# qtwo_schem.net
KiCad netlist of a schematic drawn in EAGLE
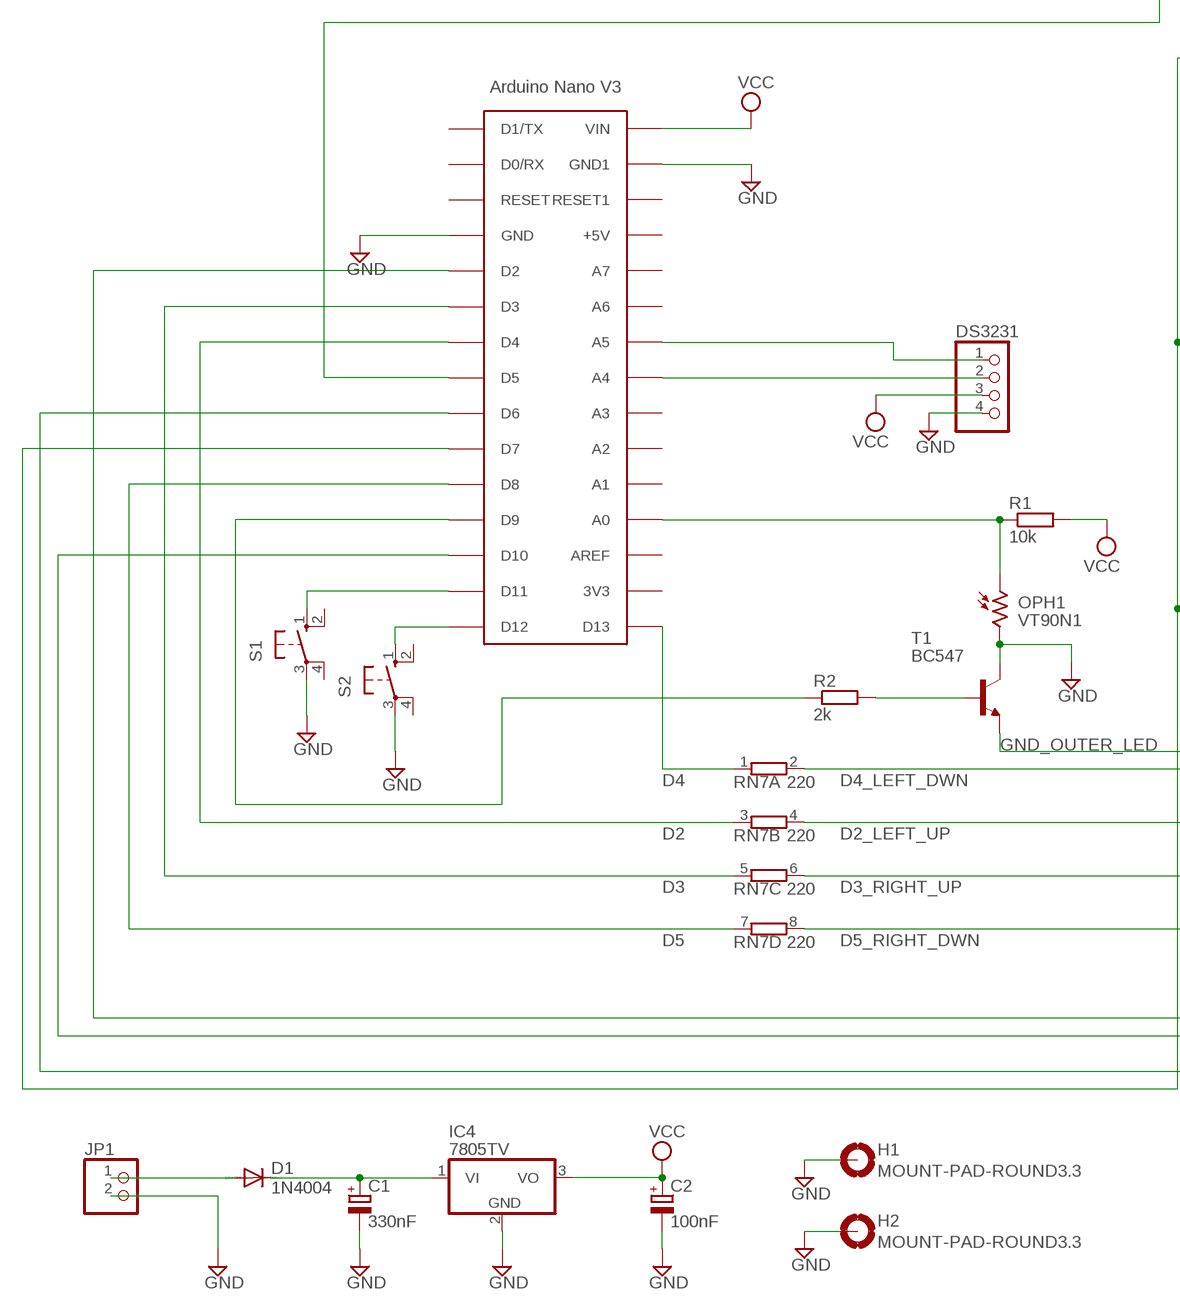
[diagram p0: schematic, sheet 1, part 1 of 2]
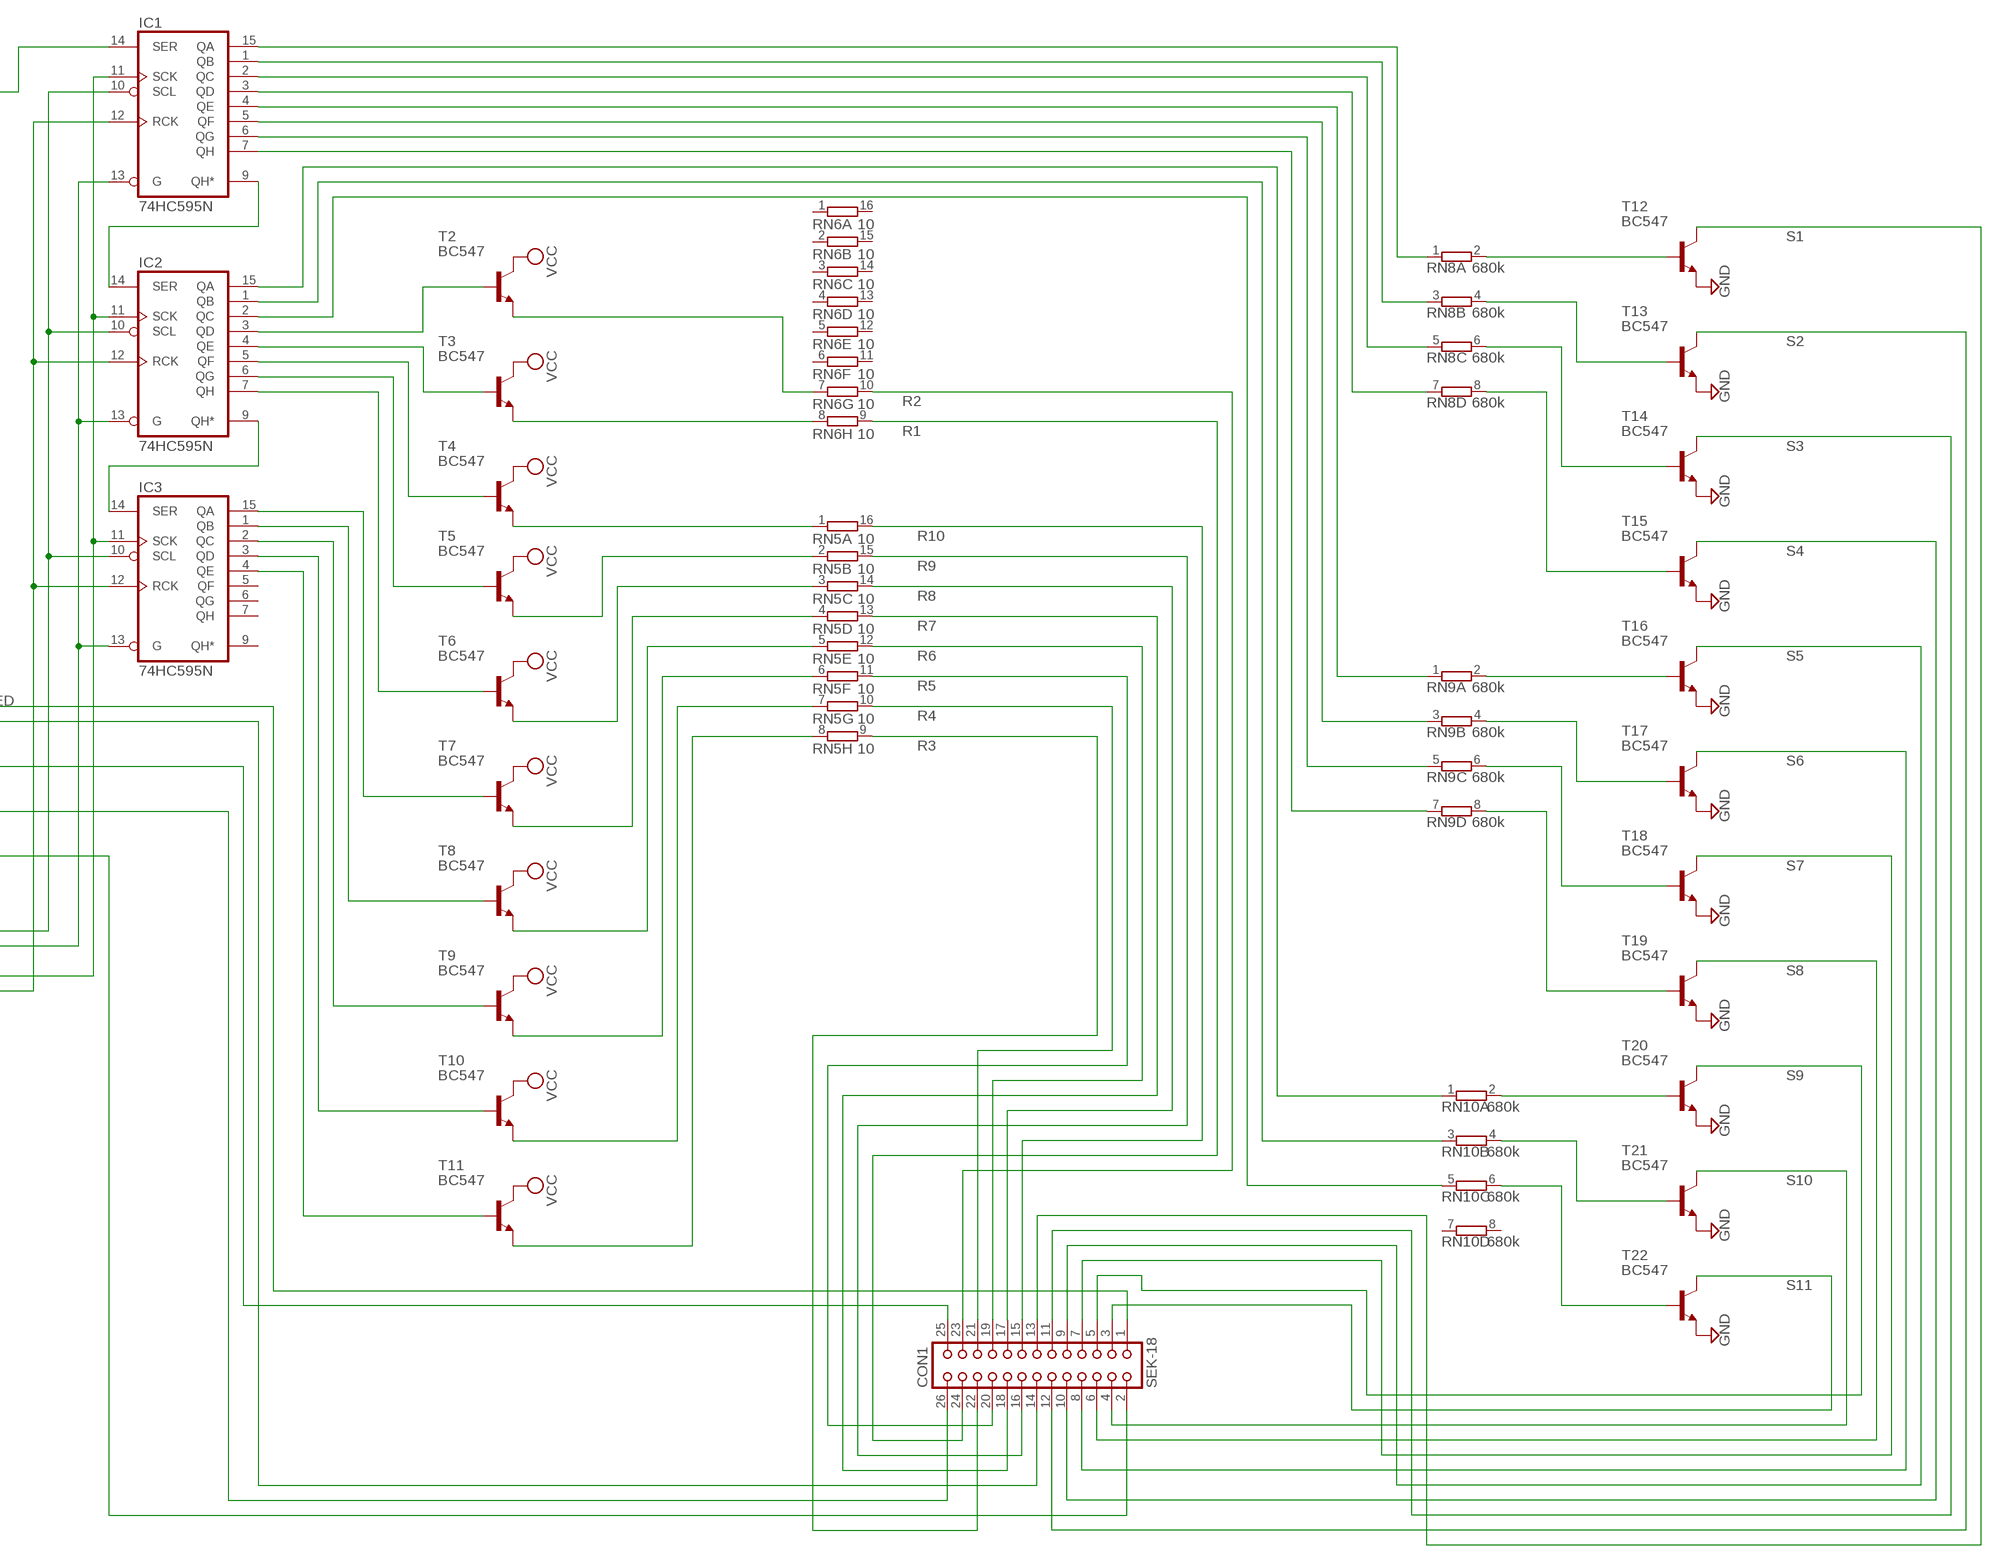
[diagram p1: schematic, sheet 1, part 2 of 2]

(export (version "E")
  (design (tool "Eeschema 10.0.6"))
  (components
    (comp (ref "C1")
      (value "330nF")
      (footprint "eagle-import:E2,5-6E")
      (libsource (lib "eagle-import") (part "CPOL-EUE2,5-6E"))
    )
    (comp (ref "C2")
      (value "100nF")
      (footprint "eagle-import:E2,5-6E")
      (libsource (lib "eagle-import") (part "CPOL-EUE2,5-6E"))
    )
    (comp (ref "CON1")
      (value "SEK-18")
      (footprint "eagle-import:CON26")
      (libsource (lib "eagle-import") (part "CON26"))
    )
    (comp (ref "D1")
      (value "1N4004")
      (footprint "eagle-import:DO41-10")
      (libsource (lib "eagle-import") (part "1N4004"))
    )
    (comp (ref "DS3231")
      (value "PINHD-1X4")
      (footprint "eagle-import:1X04")
      (libsource (lib "eagle-import") (part "PINHD-1X4"))
    )
    (comp (ref "H1")
      (value "MOUNT-PAD-ROUND3.3")
      (footprint "eagle-import:3,3-PAD")
      (libsource (lib "eagle-import") (part "MOUNT-PAD-ROUND3.3"))
    )
    (comp (ref "H2")
      (value "MOUNT-PAD-ROUND3.3")
      (footprint "eagle-import:3,3-PAD")
      (libsource (lib "eagle-import") (part "MOUNT-PAD-ROUND3.3"))
    )
    (comp (ref "IC1")
      (value "74HC595N")
      (footprint "eagle-import:DIL16")
      (libsource (lib "eagle-import") (part "74595NHC"))
    )
    (comp (ref "IC2")
      (value "74HC595N")
      (footprint "eagle-import:DIL16")
      (libsource (lib "eagle-import") (part "74595NHC"))
    )
    (comp (ref "IC3")
      (value "74HC595N")
      (footprint "eagle-import:DIL16")
      (libsource (lib "eagle-import") (part "74595NHC"))
    )
    (comp (ref "IC4")
      (value "7805TV")
      (footprint "eagle-import:TO220V")
      (libsource (lib "eagle-import") (part "78TV05"))
    )
    (comp (ref "JP1")
      (value "PINHD-1X2")
      (footprint "eagle-import:1X02")
      (libsource (lib "eagle-import") (part "PINHD-1X2"))
    )
    (comp (ref "OPH1")
      (value "VT90N1")
      (footprint "eagle-import:VT900")
      (libsource (lib "eagle-import") (part "VT90N1"))
    )
    (comp (ref "R1")
      (value "10k")
      (footprint "eagle-import:0204_7")
      (libsource (lib "eagle-import") (part "R-EU_0204/7"))
    )
    (comp (ref "R2")
      (value "2k")
      (footprint "eagle-import:0204_7")
      (libsource (lib "eagle-import") (part "R-EU_0204/7"))
    )
    (comp (ref "RN5")
      (value "10")
      (footprint "eagle-import:DIL16")
      (libsource (lib "eagle-import") (part "8R-N"))
    )
    (comp (ref "RN6")
      (value "10")
      (footprint "eagle-import:DIL16")
      (libsource (lib "eagle-import") (part "8R-N"))
    )
    (comp (ref "RN7")
      (value "220")
      (footprint "eagle-import:SIL8")
      (libsource (lib "eagle-import") (part "E4R"))
    )
    (comp (ref "RN8")
      (value "680k")
      (footprint "eagle-import:SIL8")
      (libsource (lib "eagle-import") (part "E4R"))
    )
    (comp (ref "RN9")
      (value "680k")
      (footprint "eagle-import:SIL8")
      (libsource (lib "eagle-import") (part "E4R"))
    )
    (comp (ref "RN10")
      (value "680k")
      (footprint "eagle-import:SIL8")
      (libsource (lib "eagle-import") (part "E4R"))
    )
    (comp (ref "S1")
      (value "10-XX")
      (footprint "eagle-import:B3F-10XX")
      (fields (field (name "MPN") "B3F-1000"))
      (libsource (lib "eagle-import") (part "10-XX"))
    )
    (comp (ref "S2")
      (value "10-XX")
      (footprint "eagle-import:B3F-10XX")
      (fields (field (name "MPN") "B3F-1000"))
      (libsource (lib "eagle-import") (part "10-XX"))
    )
    (comp (ref "T1")
      (value "BC547")
      (footprint "eagle-import:TO92")
      (libsource (lib "eagle-import") (part "BC547"))
    )
    (comp (ref "T2")
      (value "BC547")
      (footprint "eagle-import:TO92")
      (libsource (lib "eagle-import") (part "BC547"))
    )
    (comp (ref "T3")
      (value "BC547")
      (footprint "eagle-import:TO92")
      (libsource (lib "eagle-import") (part "BC547"))
    )
    (comp (ref "T4")
      (value "BC547")
      (footprint "eagle-import:TO92")
      (libsource (lib "eagle-import") (part "BC547"))
    )
    (comp (ref "T5")
      (value "BC547")
      (footprint "eagle-import:TO92")
      (libsource (lib "eagle-import") (part "BC547"))
    )
    (comp (ref "T6")
      (value "BC547")
      (footprint "eagle-import:TO92")
      (libsource (lib "eagle-import") (part "BC547"))
    )
    (comp (ref "T7")
      (value "BC547")
      (footprint "eagle-import:TO92")
      (libsource (lib "eagle-import") (part "BC547"))
    )
    (comp (ref "T8")
      (value "BC547")
      (footprint "eagle-import:TO92")
      (libsource (lib "eagle-import") (part "BC547"))
    )
    (comp (ref "T9")
      (value "BC547")
      (footprint "eagle-import:TO92")
      (libsource (lib "eagle-import") (part "BC547"))
    )
    (comp (ref "T10")
      (value "BC547")
      (footprint "eagle-import:TO92")
      (libsource (lib "eagle-import") (part "BC547"))
    )
    (comp (ref "T11")
      (value "BC547")
      (footprint "eagle-import:TO92")
      (libsource (lib "eagle-import") (part "BC547"))
    )
    (comp (ref "T12")
      (value "BC547")
      (footprint "eagle-import:TO92")
      (libsource (lib "eagle-import") (part "BC547"))
    )
    (comp (ref "T13")
      (value "BC547")
      (footprint "eagle-import:TO92")
      (libsource (lib "eagle-import") (part "BC547"))
    )
    (comp (ref "T14")
      (value "BC547")
      (footprint "eagle-import:TO92")
      (libsource (lib "eagle-import") (part "BC547"))
    )
    (comp (ref "T15")
      (value "BC547")
      (footprint "eagle-import:TO92")
      (libsource (lib "eagle-import") (part "BC547"))
    )
    (comp (ref "T16")
      (value "BC547")
      (footprint "eagle-import:TO92")
      (libsource (lib "eagle-import") (part "BC547"))
    )
    (comp (ref "T17")
      (value "BC547")
      (footprint "eagle-import:TO92")
      (libsource (lib "eagle-import") (part "BC547"))
    )
    (comp (ref "T18")
      (value "BC547")
      (footprint "eagle-import:TO92")
      (libsource (lib "eagle-import") (part "BC547"))
    )
    (comp (ref "T19")
      (value "BC547")
      (footprint "eagle-import:TO92")
      (libsource (lib "eagle-import") (part "BC547"))
    )
    (comp (ref "T20")
      (value "BC547")
      (footprint "eagle-import:TO92")
      (libsource (lib "eagle-import") (part "BC547"))
    )
    (comp (ref "T21")
      (value "BC547")
      (footprint "eagle-import:TO92")
      (libsource (lib "eagle-import") (part "BC547"))
    )
    (comp (ref "T22")
      (value "BC547")
      (footprint "eagle-import:TO92")
      (libsource (lib "eagle-import") (part "BC547"))
    )
    (comp (ref "U$1")
      (value "ARDUINONANO")
      (footprint "eagle-import:PDIP-32")
      (libsource (lib "eagle-import") (part "ARDUINONANO"))
    )
  )
  (nets
    (net (code "1") (name "/D2") (class "Default")
      (node (ref "RN7") (pin "3") (pinfunction "1_3") (pintype "passive"))
      (node (ref "U$1") (pin "D4") (pinfunction "D4_D4") (pintype "bidirectional"))
    )
    (net (code "2") (name "/D2_LEFT_UP") (class "Default")
      (node (ref "CON1") (pin "25") (pinfunction "25_25") (pintype "passive"))
      (node (ref "RN7") (pin "4") (pinfunction "2_4") (pintype "passive"))
    )
    (net (code "3") (name "/D3") (class "Default")
      (node (ref "RN7") (pin "5") (pinfunction "1_5") (pintype "passive"))
      (node (ref "U$1") (pin "D3") (pinfunction "D3_D3") (pintype "bidirectional"))
    )
    (net (code "4") (name "/D3_RIGHT_UP") (class "Default")
      (node (ref "CON1") (pin "26") (pinfunction "26_26") (pintype "passive"))
      (node (ref "RN7") (pin "6") (pinfunction "2_6") (pintype "passive"))
    )
    (net (code "5") (name "/D4") (class "Default")
      (node (ref "RN7") (pin "1") (pinfunction "1_1") (pintype "passive"))
      (node (ref "U$1") (pin "D13") (pinfunction "D13_D13") (pintype "bidirectional"))
    )
    (net (code "6") (name "/D4_LEFT_DWN") (class "Default")
      (node (ref "CON1") (pin "14") (pinfunction "14_14") (pintype "passive"))
      (node (ref "RN7") (pin "2") (pinfunction "2_2") (pintype "passive"))
    )
    (net (code "7") (name "/D5") (class "Default")
      (node (ref "RN7") (pin "7") (pinfunction "1_7") (pintype "passive"))
      (node (ref "U$1") (pin "D8") (pinfunction "D8_D8") (pintype "bidirectional"))
    )
    (net (code "8") (name "/D5_RIGHT_DWN") (class "Default")
      (node (ref "CON1") (pin "2") (pinfunction "2_2") (pintype "passive"))
      (node (ref "RN7") (pin "8") (pinfunction "2_8") (pintype "passive"))
    )
    (net (code "9") (name "/GND_OUTER_LED") (class "Default")
      (node (ref "CON1") (pin "1") (pinfunction "1_1") (pintype "passive"))
      (node (ref "T1") (pin "1") (pinfunction "E_1") (pintype "passive"))
    )
    (net (code "10") (name "/R1") (class "Default")
      (node (ref "CON1") (pin "24") (pinfunction "24_24") (pintype "passive"))
      (node (ref "RN6") (pin "9") (pinfunction "2_9") (pintype "passive"))
    )
    (net (code "11") (name "/R2") (class "Default")
      (node (ref "CON1") (pin "23") (pinfunction "23_23") (pintype "passive"))
      (node (ref "RN6") (pin "10") (pinfunction "2_10") (pintype "passive"))
    )
    (net (code "12") (name "/R3") (class "Default")
      (node (ref "CON1") (pin "22") (pinfunction "22_22") (pintype "passive"))
      (node (ref "RN5") (pin "9") (pinfunction "2_9") (pintype "passive"))
    )
    (net (code "13") (name "/R4") (class "Default")
      (node (ref "CON1") (pin "21") (pinfunction "21_21") (pintype "passive"))
      (node (ref "RN5") (pin "10") (pinfunction "2_10") (pintype "passive"))
    )
    (net (code "14") (name "/R5") (class "Default")
      (node (ref "CON1") (pin "20") (pinfunction "20_20") (pintype "passive"))
      (node (ref "RN5") (pin "11") (pinfunction "2_11") (pintype "passive"))
    )
    (net (code "15") (name "/R6") (class "Default")
      (node (ref "CON1") (pin "19") (pinfunction "19_19") (pintype "passive"))
      (node (ref "RN5") (pin "12") (pinfunction "2_12") (pintype "passive"))
    )
    (net (code "16") (name "/R7") (class "Default")
      (node (ref "CON1") (pin "18") (pinfunction "18_18") (pintype "passive"))
      (node (ref "RN5") (pin "13") (pinfunction "2_13") (pintype "passive"))
    )
    (net (code "17") (name "/R8") (class "Default")
      (node (ref "CON1") (pin "17") (pinfunction "17_17") (pintype "passive"))
      (node (ref "RN5") (pin "14") (pinfunction "2_14") (pintype "passive"))
    )
    (net (code "18") (name "/R9") (class "Default")
      (node (ref "CON1") (pin "16") (pinfunction "16_16") (pintype "passive"))
      (node (ref "RN5") (pin "15") (pinfunction "2_15") (pintype "passive"))
    )
    (net (code "19") (name "/R10") (class "Default")
      (node (ref "CON1") (pin "15") (pinfunction "15_15") (pintype "passive"))
      (node (ref "RN5") (pin "16") (pinfunction "2_16") (pintype "passive"))
    )
    (net (code "20") (name "/S1") (class "Default")
      (node (ref "CON1") (pin "13") (pinfunction "13_13") (pintype "passive"))
      (node (ref "T12") (pin "3") (pinfunction "C_3") (pintype "passive"))
    )
    (net (code "21") (name "/S2") (class "Default")
      (node (ref "CON1") (pin "12") (pinfunction "12_12") (pintype "passive"))
      (node (ref "T13") (pin "3") (pinfunction "C_3") (pintype "passive"))
    )
    (net (code "22") (name "/S3") (class "Default")
      (node (ref "CON1") (pin "11") (pinfunction "11_11") (pintype "passive"))
      (node (ref "T14") (pin "3") (pinfunction "C_3") (pintype "passive"))
    )
    (net (code "23") (name "/S4") (class "Default")
      (node (ref "CON1") (pin "10") (pinfunction "10_10") (pintype "passive"))
      (node (ref "T15") (pin "3") (pinfunction "C_3") (pintype "passive"))
    )
    (net (code "24") (name "/S5") (class "Default")
      (node (ref "CON1") (pin "9") (pinfunction "9_9") (pintype "passive"))
      (node (ref "T16") (pin "3") (pinfunction "C_3") (pintype "passive"))
    )
    (net (code "25") (name "/S6") (class "Default")
      (node (ref "CON1") (pin "8") (pinfunction "8_8") (pintype "passive"))
      (node (ref "T17") (pin "3") (pinfunction "C_3") (pintype "passive"))
    )
    (net (code "26") (name "/S7") (class "Default")
      (node (ref "CON1") (pin "7") (pinfunction "7_7") (pintype "passive"))
      (node (ref "T18") (pin "3") (pinfunction "C_3") (pintype "passive"))
    )
    (net (code "27") (name "/S8") (class "Default")
      (node (ref "CON1") (pin "6") (pinfunction "6_6") (pintype "passive"))
      (node (ref "T19") (pin "3") (pinfunction "C_3") (pintype "passive"))
    )
    (net (code "28") (name "/S9") (class "Default")
      (node (ref "CON1") (pin "5") (pinfunction "5_5") (pintype "passive"))
      (node (ref "T20") (pin "3") (pinfunction "C_3") (pintype "passive"))
    )
    (net (code "29") (name "/S10") (class "Default")
      (node (ref "CON1") (pin "4") (pinfunction "4_4") (pintype "passive"))
      (node (ref "T21") (pin "3") (pinfunction "C_3") (pintype "passive"))
    )
    (net (code "30") (name "/S11") (class "Default")
      (node (ref "CON1") (pin "3") (pinfunction "3_3") (pintype "passive"))
      (node (ref "T22") (pin "3") (pinfunction "C_3") (pintype "passive"))
    )
    (net (code "31") (name "GND") (class "Default")
      (node (ref "C1") (pin "-") (pinfunction "-_-") (pintype "passive"))
      (node (ref "C2") (pin "-") (pinfunction "-_-") (pintype "passive"))
      (node (ref "DS3231") (pin "4") (pinfunction "4_4") (pintype "passive"))
      (node (ref "H1") (pin "B3,3") (pinfunction "MOUNT_B3,3") (pintype "passive"))
      (node (ref "H2") (pin "B3,3") (pinfunction "MOUNT_B3,3") (pintype "passive"))
      (node (ref "IC4") (pin "2") (pinfunction "GND_2") (pintype "passive"))
      (node (ref "JP1") (pin "2") (pinfunction "2_2") (pintype "passive"))
      (node (ref "OPH1") (pin "2") (pinfunction "2_2") (pintype "passive"))
      (node (ref "S1") (pin "3") (pinfunction "P_3") (pintype "passive"))
      (node (ref "S2") (pin "3") (pinfunction "P_3") (pintype "passive"))
      (node (ref "T1") (pin "3") (pinfunction "C_3") (pintype "passive"))
      (node (ref "T12") (pin "1") (pinfunction "E_1") (pintype "passive"))
      (node (ref "T13") (pin "1") (pinfunction "E_1") (pintype "passive"))
      (node (ref "T14") (pin "1") (pinfunction "E_1") (pintype "passive"))
      (node (ref "T15") (pin "1") (pinfunction "E_1") (pintype "passive"))
      (node (ref "T16") (pin "1") (pinfunction "E_1") (pintype "passive"))
      (node (ref "T17") (pin "1") (pinfunction "E_1") (pintype "passive"))
      (node (ref "T18") (pin "1") (pinfunction "E_1") (pintype "passive"))
      (node (ref "T19") (pin "1") (pinfunction "E_1") (pintype "passive"))
      (node (ref "T20") (pin "1") (pinfunction "E_1") (pintype "passive"))
      (node (ref "T21") (pin "1") (pinfunction "E_1") (pintype "passive"))
      (node (ref "T22") (pin "1") (pinfunction "E_1") (pintype "passive"))
      (node (ref "U$1") (pin "GND") (pinfunction "GND_GND") (pintype "bidirectional"))
      (node (ref "U$1") (pin "GND1") (pinfunction "GND1_GND1") (pintype "bidirectional"))
    )
    (net (code "32") (name "Net-(D1-PadA)") (class "Default")
      (node (ref "D1") (pin "A") (pinfunction "A_A") (pintype "passive"))
      (node (ref "JP1") (pin "1") (pinfunction "1_1") (pintype "passive"))
    )
    (net (code "33") (name "Net-(IC1A-G)") (class "Default")
      (node (ref "IC1") (pin "13") (pinfunction "G_13") (pintype "input"))
      (node (ref "IC2") (pin "13") (pinfunction "G_13") (pintype "input"))
      (node (ref "IC3") (pin "13") (pinfunction "G_13") (pintype "input"))
      (node (ref "U$1") (pin "D10") (pinfunction "D10_D10") (pintype "bidirectional"))
    )
    (net (code "34") (name "Net-(IC1A-QA)") (class "Default")
      (node (ref "IC1") (pin "15") (pinfunction "QA_15") (pintype "tri_state"))
      (node (ref "RN8") (pin "1") (pinfunction "1_1") (pintype "passive"))
    )
    (net (code "35") (name "Net-(IC1A-QB)") (class "Default")
      (node (ref "IC1") (pin "1") (pinfunction "QB_1") (pintype "tri_state"))
      (node (ref "RN8") (pin "3") (pinfunction "1_3") (pintype "passive"))
    )
    (net (code "36") (name "Net-(IC1A-QC)") (class "Default")
      (node (ref "IC1") (pin "2") (pinfunction "QC_2") (pintype "tri_state"))
      (node (ref "RN8") (pin "5") (pinfunction "1_5") (pintype "passive"))
    )
    (net (code "37") (name "Net-(IC1A-QD)") (class "Default")
      (node (ref "IC1") (pin "3") (pinfunction "QD_3") (pintype "tri_state"))
      (node (ref "RN8") (pin "7") (pinfunction "1_7") (pintype "passive"))
    )
    (net (code "38") (name "Net-(IC1A-QE)") (class "Default")
      (node (ref "IC1") (pin "4") (pinfunction "QE_4") (pintype "tri_state"))
      (node (ref "RN9") (pin "1") (pinfunction "1_1") (pintype "passive"))
    )
    (net (code "39") (name "Net-(IC1A-QF)") (class "Default")
      (node (ref "IC1") (pin "5") (pinfunction "QF_5") (pintype "tri_state"))
      (node (ref "RN9") (pin "3") (pinfunction "1_3") (pintype "passive"))
    )
    (net (code "40") (name "Net-(IC1A-QG)") (class "Default")
      (node (ref "IC1") (pin "6") (pinfunction "QG_6") (pintype "tri_state"))
      (node (ref "RN9") (pin "5") (pinfunction "1_5") (pintype "passive"))
    )
    (net (code "41") (name "Net-(IC1A-QH)") (class "Default")
      (node (ref "IC1") (pin "7") (pinfunction "QH_7") (pintype "tri_state"))
      (node (ref "RN9") (pin "7") (pinfunction "1_7") (pintype "passive"))
    )
    (net (code "42") (name "Net-(IC1A-QH*)") (class "Default")
      (node (ref "IC1") (pin "9") (pinfunction "QH*_9") (pintype "tri_state"))
      (node (ref "IC2") (pin "14") (pinfunction "SER_14") (pintype "input"))
    )
    (net (code "43") (name "Net-(IC1A-RCK)") (class "Default")
      (node (ref "IC1") (pin "12") (pinfunction "RCK_12") (pintype "input"))
      (node (ref "IC2") (pin "12") (pinfunction "RCK_12") (pintype "input"))
      (node (ref "IC3") (pin "12") (pinfunction "RCK_12") (pintype "input"))
      (node (ref "U$1") (pin "D7") (pinfunction "D7_D7") (pintype "bidirectional"))
    )
    (net (code "44") (name "Net-(IC1A-SCK)") (class "Default")
      (node (ref "IC1") (pin "11") (pinfunction "SCK_11") (pintype "input"))
      (node (ref "IC2") (pin "11") (pinfunction "SCK_11") (pintype "input"))
      (node (ref "IC3") (pin "11") (pinfunction "SCK_11") (pintype "input"))
      (node (ref "U$1") (pin "D6") (pinfunction "D6_D6") (pintype "bidirectional"))
    )
    (net (code "45") (name "Net-(IC1A-SCL)") (class "Default")
      (node (ref "IC1") (pin "10") (pinfunction "SCL_10") (pintype "input"))
      (node (ref "IC2") (pin "10") (pinfunction "SCL_10") (pintype "input"))
      (node (ref "IC3") (pin "10") (pinfunction "SCL_10") (pintype "input"))
      (node (ref "U$1") (pin "D2") (pinfunction "D2_D2") (pintype "bidirectional"))
    )
    (net (code "46") (name "Net-(IC1A-SER)") (class "Default")
      (node (ref "IC1") (pin "14") (pinfunction "SER_14") (pintype "input"))
      (node (ref "U$1") (pin "D5") (pinfunction "D5_D5") (pintype "bidirectional"))
    )
    (net (code "47") (name "Net-(IC2A-QA)") (class "Default")
      (node (ref "IC2") (pin "15") (pinfunction "QA_15") (pintype "tri_state"))
      (node (ref "RN10") (pin "1") (pinfunction "1_1") (pintype "passive"))
    )
    (net (code "48") (name "Net-(IC2A-QB)") (class "Default")
      (node (ref "IC2") (pin "1") (pinfunction "QB_1") (pintype "tri_state"))
      (node (ref "RN10") (pin "3") (pinfunction "1_3") (pintype "passive"))
    )
    (net (code "49") (name "Net-(IC2A-QC)") (class "Default")
      (node (ref "IC2") (pin "2") (pinfunction "QC_2") (pintype "tri_state"))
      (node (ref "RN10") (pin "5") (pinfunction "1_5") (pintype "passive"))
    )
    (net (code "50") (name "Net-(IC2A-QD)") (class "Default")
      (node (ref "IC2") (pin "3") (pinfunction "QD_3") (pintype "tri_state"))
      (node (ref "T2") (pin "2") (pinfunction "B_2") (pintype "passive"))
    )
    (net (code "51") (name "Net-(IC2A-QE)") (class "Default")
      (node (ref "IC2") (pin "4") (pinfunction "QE_4") (pintype "tri_state"))
      (node (ref "T3") (pin "2") (pinfunction "B_2") (pintype "passive"))
    )
    (net (code "52") (name "Net-(IC2A-QF)") (class "Default")
      (node (ref "IC2") (pin "5") (pinfunction "QF_5") (pintype "tri_state"))
      (node (ref "T4") (pin "2") (pinfunction "B_2") (pintype "passive"))
    )
    (net (code "53") (name "Net-(IC2A-QG)") (class "Default")
      (node (ref "IC2") (pin "6") (pinfunction "QG_6") (pintype "tri_state"))
      (node (ref "T5") (pin "2") (pinfunction "B_2") (pintype "passive"))
    )
    (net (code "54") (name "Net-(IC2A-QH)") (class "Default")
      (node (ref "IC2") (pin "7") (pinfunction "QH_7") (pintype "tri_state"))
      (node (ref "T6") (pin "2") (pinfunction "B_2") (pintype "passive"))
    )
    (net (code "55") (name "Net-(IC2A-QH*)") (class "Default")
      (node (ref "IC2") (pin "9") (pinfunction "QH*_9") (pintype "tri_state"))
      (node (ref "IC3") (pin "14") (pinfunction "SER_14") (pintype "input"))
    )
    (net (code "56") (name "Net-(IC3A-QA)") (class "Default")
      (node (ref "IC3") (pin "15") (pinfunction "QA_15") (pintype "tri_state"))
      (node (ref "T7") (pin "2") (pinfunction "B_2") (pintype "passive"))
    )
    (net (code "57") (name "Net-(IC3A-QB)") (class "Default")
      (node (ref "IC3") (pin "1") (pinfunction "QB_1") (pintype "tri_state"))
      (node (ref "T8") (pin "2") (pinfunction "B_2") (pintype "passive"))
    )
    (net (code "58") (name "Net-(IC3A-QC)") (class "Default")
      (node (ref "IC3") (pin "2") (pinfunction "QC_2") (pintype "tri_state"))
      (node (ref "T9") (pin "2") (pinfunction "B_2") (pintype "passive"))
    )
    (net (code "59") (name "Net-(IC3A-QD)") (class "Default")
      (node (ref "IC3") (pin "3") (pinfunction "QD_3") (pintype "tri_state"))
      (node (ref "T10") (pin "2") (pinfunction "B_2") (pintype "passive"))
    )
    (net (code "60") (name "Net-(IC3A-QE)") (class "Default")
      (node (ref "IC3") (pin "4") (pinfunction "QE_4") (pintype "tri_state"))
      (node (ref "T11") (pin "2") (pinfunction "B_2") (pintype "passive"))
    )
    (net (code "61") (name "Net-(IC4-VI)") (class "Default")
      (node (ref "C1") (pin "+") (pinfunction "+_+") (pintype "passive"))
      (node (ref "D1") (pin "C") (pinfunction "C_C") (pintype "passive"))
      (node (ref "IC4") (pin "1") (pinfunction "VI_1") (pintype "input"))
    )
    (net (code "62") (name "Net-(R2-Pad1)") (class "Default")
      (node (ref "R2") (pin "1") (pinfunction "1_1") (pintype "passive"))
      (node (ref "U$1") (pin "D9") (pinfunction "D9_D9") (pintype "bidirectional"))
    )
    (net (code "63") (name "Net-(RN5B-1)") (class "Default")
      (node (ref "RN5") (pin "2") (pinfunction "1_2") (pintype "passive"))
      (node (ref "T5") (pin "1") (pinfunction "E_1") (pintype "passive"))
    )
    (net (code "64") (name "Net-(RN5C-1)") (class "Default")
      (node (ref "RN5") (pin "3") (pinfunction "1_3") (pintype "passive"))
      (node (ref "T6") (pin "1") (pinfunction "E_1") (pintype "passive"))
    )
    (net (code "65") (name "Net-(RN5D-1)") (class "Default")
      (node (ref "RN5") (pin "4") (pinfunction "1_4") (pintype "passive"))
      (node (ref "T7") (pin "1") (pinfunction "E_1") (pintype "passive"))
    )
    (net (code "66") (name "Net-(RN5E-1)") (class "Default")
      (node (ref "RN5") (pin "5") (pinfunction "1_5") (pintype "passive"))
      (node (ref "T8") (pin "1") (pinfunction "E_1") (pintype "passive"))
    )
    (net (code "67") (name "Net-(RN5F-1)") (class "Default")
      (node (ref "RN5") (pin "6") (pinfunction "1_6") (pintype "passive"))
      (node (ref "T9") (pin "1") (pinfunction "E_1") (pintype "passive"))
    )
    (net (code "68") (name "Net-(RN5G-1)") (class "Default")
      (node (ref "RN5") (pin "7") (pinfunction "1_7") (pintype "passive"))
      (node (ref "T10") (pin "1") (pinfunction "E_1") (pintype "passive"))
    )
    (net (code "69") (name "Net-(RN5H-1)") (class "Default")
      (node (ref "RN5") (pin "8") (pinfunction "1_8") (pintype "passive"))
      (node (ref "T11") (pin "1") (pinfunction "E_1") (pintype "passive"))
    )
    (net (code "70") (name "Net-(RN6G-1)") (class "Default")
      (node (ref "RN6") (pin "7") (pinfunction "1_7") (pintype "passive"))
      (node (ref "T2") (pin "1") (pinfunction "E_1") (pintype "passive"))
    )
    (net (code "71") (name "Net-(RN6H-1)") (class "Default")
      (node (ref "RN6") (pin "8") (pinfunction "1_8") (pintype "passive"))
      (node (ref "T3") (pin "1") (pinfunction "E_1") (pintype "passive"))
    )
    (net (code "72") (name "Net-(RN8B-2)") (class "Default")
      (node (ref "RN8") (pin "4") (pinfunction "2_4") (pintype "passive"))
      (node (ref "T13") (pin "2") (pinfunction "B_2") (pintype "passive"))
    )
    (net (code "73") (name "Net-(RN8C-2)") (class "Default")
      (node (ref "RN8") (pin "6") (pinfunction "2_6") (pintype "passive"))
      (node (ref "T14") (pin "2") (pinfunction "B_2") (pintype "passive"))
    )
    (net (code "74") (name "Net-(RN8D-2)") (class "Default")
      (node (ref "RN8") (pin "8") (pinfunction "2_8") (pintype "passive"))
      (node (ref "T15") (pin "2") (pinfunction "B_2") (pintype "passive"))
    )
    (net (code "75") (name "Net-(RN9B-2)") (class "Default")
      (node (ref "RN9") (pin "4") (pinfunction "2_4") (pintype "passive"))
      (node (ref "T17") (pin "2") (pinfunction "B_2") (pintype "passive"))
    )
    (net (code "76") (name "Net-(RN9C-2)") (class "Default")
      (node (ref "RN9") (pin "6") (pinfunction "2_6") (pintype "passive"))
      (node (ref "T18") (pin "2") (pinfunction "B_2") (pintype "passive"))
    )
    (net (code "77") (name "Net-(RN9D-2)") (class "Default")
      (node (ref "RN9") (pin "8") (pinfunction "2_8") (pintype "passive"))
      (node (ref "T19") (pin "2") (pinfunction "B_2") (pintype "passive"))
    )
    (net (code "78") (name "Net-(RN10B-2)") (class "Default")
      (node (ref "RN10") (pin "4") (pinfunction "2_4") (pintype "passive"))
      (node (ref "T21") (pin "2") (pinfunction "B_2") (pintype "passive"))
    )
    (net (code "79") (name "Net-(RN10C-2)") (class "Default")
      (node (ref "RN10") (pin "6") (pinfunction "2_6") (pintype "passive"))
      (node (ref "T22") (pin "2") (pinfunction "B_2") (pintype "passive"))
    )
    (net (code "80") (name "Net-(S1-S)") (class "Default")
      (node (ref "S1") (pin "1") (pinfunction "S_1") (pintype "passive"))
      (node (ref "U$1") (pin "D11") (pinfunction "D11_D11") (pintype "bidirectional"))
    )
    (net (code "81") (name "Net-(S2-S)") (class "Default")
      (node (ref "S2") (pin "1") (pinfunction "S_1") (pintype "passive"))
      (node (ref "U$1") (pin "D12") (pinfunction "D12_D12") (pintype "bidirectional"))
    )
    (net (code "82") (name "Net-(T1-B)") (class "Default")
      (node (ref "R2") (pin "2") (pinfunction "2_2") (pintype "passive"))
      (node (ref "T1") (pin "2") (pinfunction "B_2") (pintype "passive"))
    )
    (net (code "83") (name "Net-(T4-E)") (class "Default")
      (node (ref "RN5") (pin "1") (pinfunction "1_1") (pintype "passive"))
      (node (ref "T4") (pin "1") (pinfunction "E_1") (pintype "passive"))
    )
    (net (code "84") (name "Net-(T12-B)") (class "Default")
      (node (ref "RN8") (pin "2") (pinfunction "2_2") (pintype "passive"))
      (node (ref "T12") (pin "2") (pinfunction "B_2") (pintype "passive"))
    )
    (net (code "85") (name "Net-(T16-B)") (class "Default")
      (node (ref "RN9") (pin "2") (pinfunction "2_2") (pintype "passive"))
      (node (ref "T16") (pin "2") (pinfunction "B_2") (pintype "passive"))
    )
    (net (code "86") (name "Net-(T20-B)") (class "Default")
      (node (ref "RN10") (pin "2") (pinfunction "2_2") (pintype "passive"))
      (node (ref "T20") (pin "2") (pinfunction "B_2") (pintype "passive"))
    )
    (net (code "87") (name "Net-(U$1-A0)") (class "Default")
      (node (ref "OPH1") (pin "1") (pinfunction "1_1") (pintype "passive"))
      (node (ref "R1") (pin "1") (pinfunction "1_1") (pintype "passive"))
      (node (ref "U$1") (pin "A7") (pinfunction "A0_A7") (pintype "bidirectional"))
    )
    (net (code "88") (name "Net-(U$1-A4)") (class "Default")
      (node (ref "DS3231") (pin "2") (pinfunction "2_2") (pintype "passive"))
      (node (ref "U$1") (pin "A3") (pinfunction "A4_A3") (pintype "bidirectional"))
    )
    (net (code "89") (name "Net-(U$1-A5)") (class "Default")
      (node (ref "DS3231") (pin "1") (pinfunction "1_1") (pintype "passive"))
      (node (ref "U$1") (pin "A2") (pinfunction "A5_A2") (pintype "bidirectional"))
    )
    (net (code "90") (name "VCC") (class "Default")
      (node (ref "C2") (pin "+") (pinfunction "+_+") (pintype "passive"))
      (node (ref "DS3231") (pin "3") (pinfunction "3_3") (pintype "passive"))
      (node (ref "IC4") (pin "3") (pinfunction "VO_3") (pintype "passive"))
      (node (ref "R1") (pin "2") (pinfunction "2_2") (pintype "passive"))
      (node (ref "T10") (pin "3") (pinfunction "C_3") (pintype "passive"))
      (node (ref "T11") (pin "3") (pinfunction "C_3") (pintype "passive"))
      (node (ref "T2") (pin "3") (pinfunction "C_3") (pintype "passive"))
      (node (ref "T3") (pin "3") (pinfunction "C_3") (pintype "passive"))
      (node (ref "T4") (pin "3") (pinfunction "C_3") (pintype "passive"))
      (node (ref "T5") (pin "3") (pinfunction "C_3") (pintype "passive"))
      (node (ref "T6") (pin "3") (pinfunction "C_3") (pintype "passive"))
      (node (ref "T7") (pin "3") (pinfunction "C_3") (pintype "passive"))
      (node (ref "T8") (pin "3") (pinfunction "C_3") (pintype "passive"))
      (node (ref "T9") (pin "3") (pinfunction "C_3") (pintype "passive"))
      (node (ref "U$1") (pin "VIN") (pinfunction "VIN_VIN") (pintype "bidirectional"))
    )
    (net (code "91") (name "unconnected-(IC3A-QF-Pad5)") (class "Default")
      (node (ref "IC3") (pin "5") (pinfunction "QF_5") (pintype "tri_state"))
    )
    (net (code "92") (name "unconnected-(IC3A-QG-Pad6)") (class "Default")
      (node (ref "IC3") (pin "6") (pinfunction "QG_6") (pintype "tri_state"))
    )
    (net (code "93") (name "unconnected-(IC3A-QH*-Pad9)") (class "Default")
      (node (ref "IC3") (pin "9") (pinfunction "QH*_9") (pintype "tri_state"))
    )
    (net (code "94") (name "unconnected-(IC3A-QH-Pad7)") (class "Default")
      (node (ref "IC3") (pin "7") (pinfunction "QH_7") (pintype "tri_state"))
    )
    (net (code "95") (name "unconnected-(RN6-Pad1)") (class "Default")
      (node (ref "RN6") (pin "1") (pinfunction "1_1") (pintype "passive"))
    )
    (net (code "96") (name "unconnected-(RN6A-2-Pad16)") (class "Default")
      (node (ref "RN6") (pin "16") (pinfunction "2_16") (pintype "passive"))
    )
    (net (code "97") (name "unconnected-(RN6B-1-Pad2)") (class "Default")
      (node (ref "RN6") (pin "2") (pinfunction "1_2") (pintype "passive"))
    )
    (net (code "98") (name "unconnected-(RN6B-2-Pad15)") (class "Default")
      (node (ref "RN6") (pin "15") (pinfunction "2_15") (pintype "passive"))
    )
    (net (code "99") (name "unconnected-(RN6C-1-Pad3)") (class "Default")
      (node (ref "RN6") (pin "3") (pinfunction "1_3") (pintype "passive"))
    )
    (net (code "100") (name "unconnected-(RN6C-2-Pad14)") (class "Default")
      (node (ref "RN6") (pin "14") (pinfunction "2_14") (pintype "passive"))
    )
    (net (code "101") (name "unconnected-(RN6D-1-Pad4)") (class "Default")
      (node (ref "RN6") (pin "4") (pinfunction "1_4") (pintype "passive"))
    )
    (net (code "102") (name "unconnected-(RN6D-2-Pad13)") (class "Default")
      (node (ref "RN6") (pin "13") (pinfunction "2_13") (pintype "passive"))
    )
    (net (code "103") (name "unconnected-(RN6E-1-Pad5)") (class "Default")
      (node (ref "RN6") (pin "5") (pinfunction "1_5") (pintype "passive"))
    )
    (net (code "104") (name "unconnected-(RN6E-2-Pad12)") (class "Default")
      (node (ref "RN6") (pin "12") (pinfunction "2_12") (pintype "passive"))
    )
    (net (code "105") (name "unconnected-(RN6F-1-Pad6)") (class "Default")
      (node (ref "RN6") (pin "6") (pinfunction "1_6") (pintype "passive"))
    )
    (net (code "106") (name "unconnected-(RN6F-2-Pad11)") (class "Default")
      (node (ref "RN6") (pin "11") (pinfunction "2_11") (pintype "passive"))
    )
    (net (code "107") (name "unconnected-(RN10D-1-Pad7)") (class "Default")
      (node (ref "RN10") (pin "7") (pinfunction "1_7") (pintype "passive"))
    )
    (net (code "108") (name "unconnected-(RN10D-2-Pad8)") (class "Default")
      (node (ref "RN10") (pin "8") (pinfunction "2_8") (pintype "passive"))
    )
    (net (code "109") (name "unconnected-(S1-P1-Pad4)") (class "Default")
      (node (ref "S1") (pin "4") (pinfunction "P1_4") (pintype "passive"))
    )
    (net (code "110") (name "unconnected-(S1-S1-Pad2)") (class "Default")
      (node (ref "S1") (pin "2") (pinfunction "S1_2") (pintype "passive"))
    )
    (net (code "111") (name "unconnected-(S2-P1-Pad4)") (class "Default")
      (node (ref "S2") (pin "4") (pinfunction "P1_4") (pintype "passive"))
    )
    (net (code "112") (name "unconnected-(S2-S1-Pad2)") (class "Default")
      (node (ref "S2") (pin "2") (pinfunction "S1_2") (pintype "passive"))
    )
    (net (code "113") (name "unconnected-(U$1-A1-PadA6)") (class "Default")
      (node (ref "U$1") (pin "A6") (pinfunction "A1_A6") (pintype "bidirectional"))
    )
    (net (code "114") (name "unconnected-(U$1-A2-PadA5)") (class "Default")
      (node (ref "U$1") (pin "A5") (pinfunction "A2_A5") (pintype "bidirectional"))
    )
    (net (code "115") (name "unconnected-(U$1-A3-PadA4)") (class "Default")
      (node (ref "U$1") (pin "A4") (pinfunction "A3_A4") (pintype "bidirectional"))
    )
    (net (code "116") (name "unconnected-(U$1-A6-PadA1)") (class "Default")
      (node (ref "U$1") (pin "A1") (pinfunction "A6_A1") (pintype "bidirectional"))
    )
    (net (code "117") (name "unconnected-(U$1-A7-PadA0)") (class "Default")
      (node (ref "U$1") (pin "A0") (pinfunction "A7_A0") (pintype "bidirectional"))
    )
    (net (code "118") (name "unconnected-(U$1-Pad+5V)") (class "Default")
      (node (ref "U$1") (pin "+5V") (pinfunction "+5V_+5V") (pintype "bidirectional"))
    )
    (net (code "119") (name "unconnected-(U$1-Pad3V3)") (class "Default")
      (node (ref "U$1") (pin "3V3") (pinfunction "3V3_3V3") (pintype "bidirectional"))
    )
    (net (code "120") (name "unconnected-(U$1-PadAREF)") (class "Default")
      (node (ref "U$1") (pin "AREF") (pinfunction "AREF_AREF") (pintype "bidirectional"))
    )
    (net (code "121") (name "unconnected-(U$1-PadD0{slash}RX)") (class "Default")
      (node (ref "U$1") (pin "D0/RX") (pinfunction "D0/RX_D0/RX") (pintype "bidirectional"))
    )
    (net (code "122") (name "unconnected-(U$1-PadD1{slash}TX)") (class "Default")
      (node (ref "U$1") (pin "D1/TX") (pinfunction "D1/TX_D1/TX") (pintype "bidirectional"))
    )
    (net (code "123") (name "unconnected-(U$1-PadRESET)") (class "Default")
      (node (ref "U$1") (pin "RESET") (pinfunction "RESET_RESET") (pintype "bidirectional"))
    )
    (net (code "124") (name "unconnected-(U$1-PadRESET1)") (class "Default")
      (node (ref "U$1") (pin "RESET1") (pinfunction "RESET1_RESET1") (pintype "bidirectional"))
    )
  )
)
